# p8x-memory-card.net
KiCad netlist of a schematic drawn in EAGLE
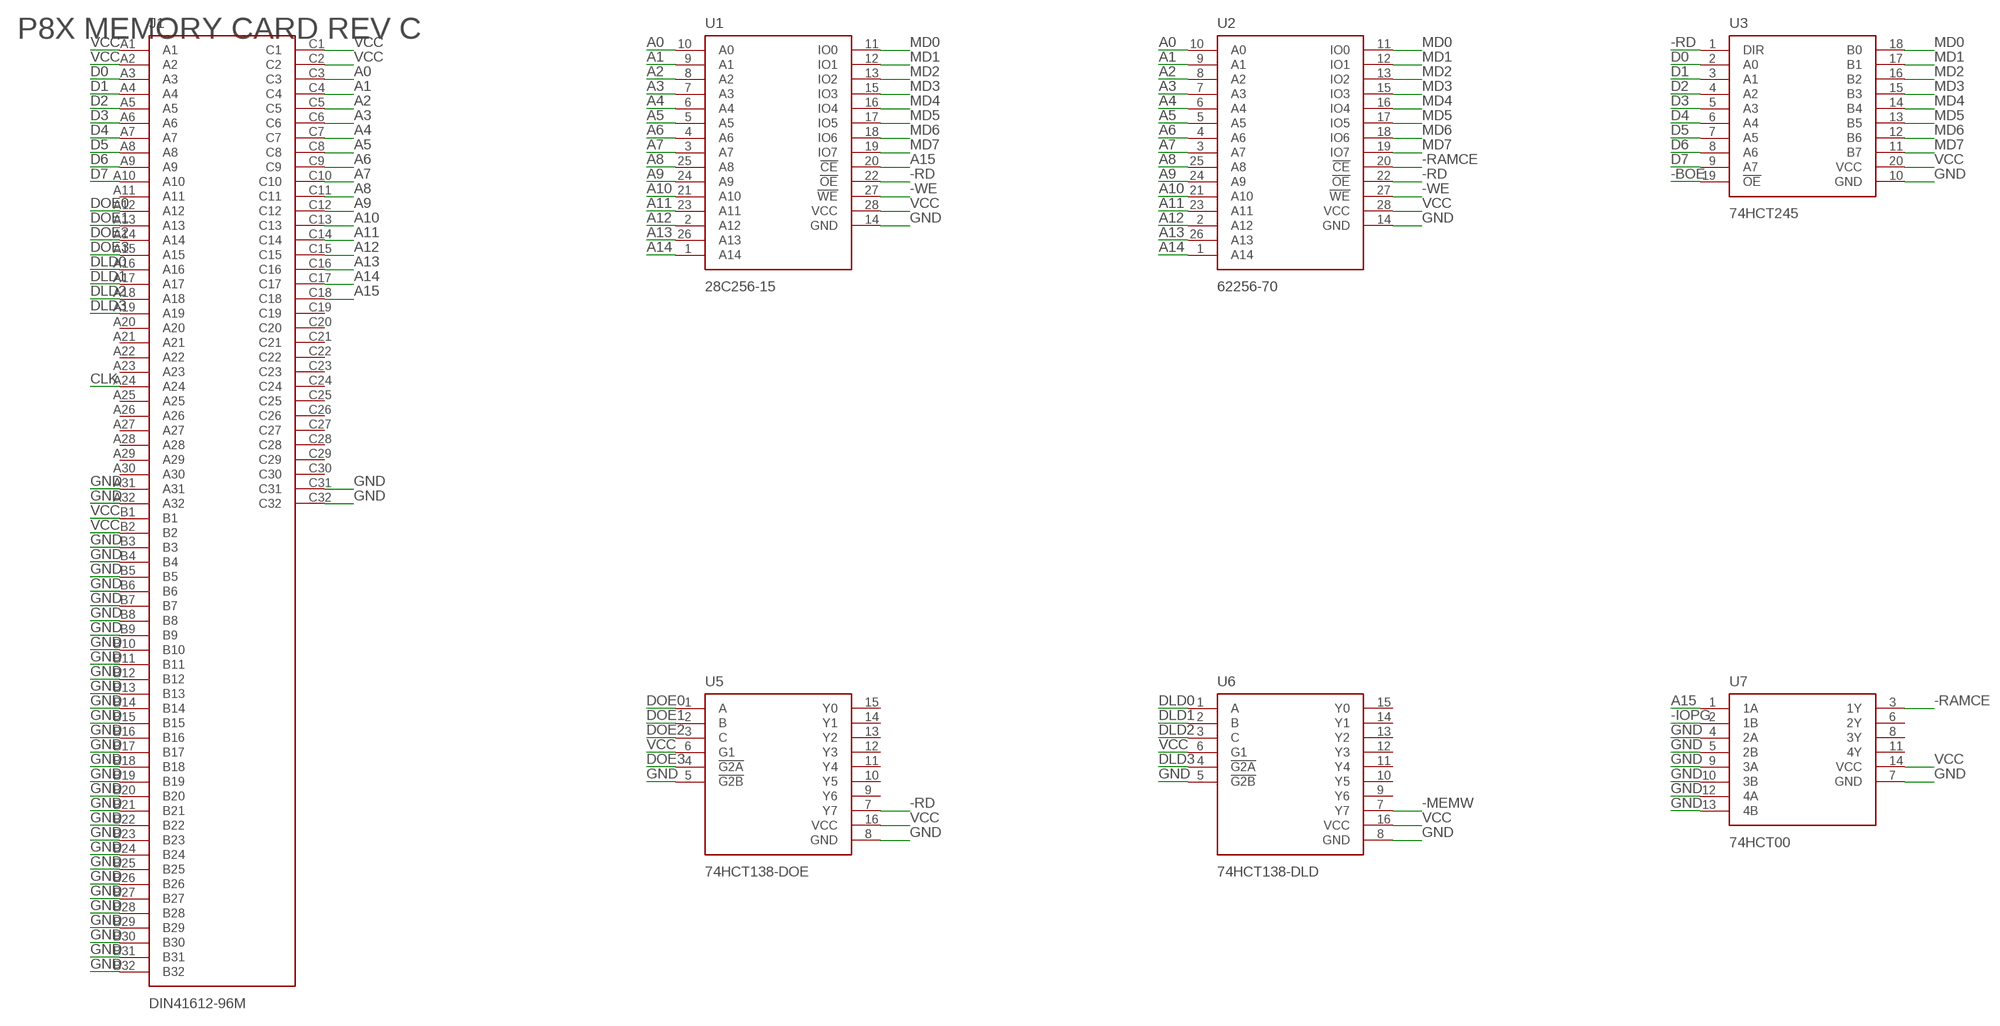
[diagram p0: schematic, sheet 1, part 1 of 2]
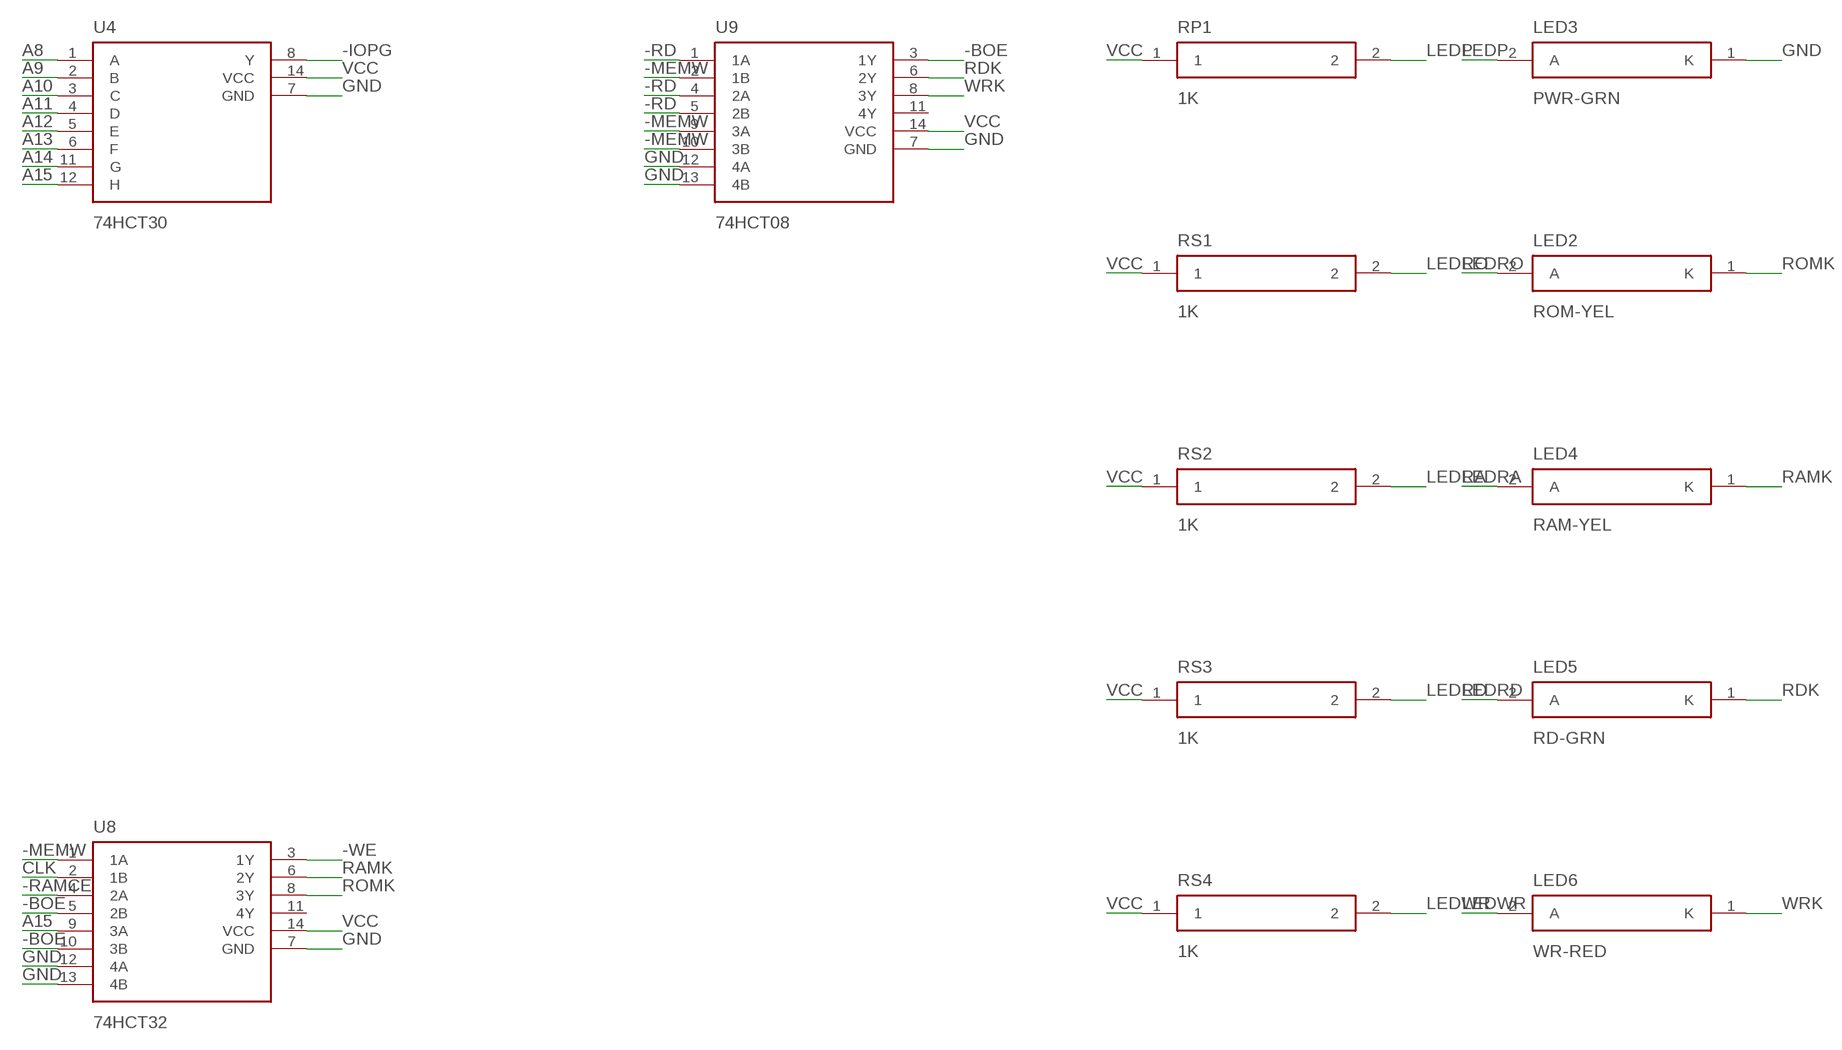
[diagram p1: schematic, sheet 1, part 2 of 2]

(export (version "E")
  (design (tool "Eeschema 10.0.6"))
  (components
    (comp (ref "J1")
      (value "DIN41612-96M")
      (footprint "eagle-import:DIN96")
      (libsource (lib "eagle-import") (part "DIN96"))
    )
    (comp (ref "LED2")
      (value "ROM-YEL")
      (footprint "eagle-import:LED5")
      (libsource (lib "eagle-import") (part "LED"))
    )
    (comp (ref "LED3")
      (value "PWR-GRN")
      (footprint "eagle-import:LED5")
      (libsource (lib "eagle-import") (part "LED"))
    )
    (comp (ref "LED4")
      (value "RAM-YEL")
      (footprint "eagle-import:LED5")
      (libsource (lib "eagle-import") (part "LED"))
    )
    (comp (ref "LED5")
      (value "RD-GRN")
      (footprint "eagle-import:LED5")
      (libsource (lib "eagle-import") (part "LED"))
    )
    (comp (ref "LED6")
      (value "WR-RED")
      (footprint "eagle-import:LED5")
      (libsource (lib "eagle-import") (part "LED"))
    )
    (comp (ref "RP1")
      (value "1K")
      (footprint "eagle-import:R_AXIAL")
      (libsource (lib "eagle-import") (part "RES"))
    )
    (comp (ref "RS1")
      (value "1K")
      (footprint "eagle-import:R_AXIAL")
      (libsource (lib "eagle-import") (part "RES"))
    )
    (comp (ref "RS2")
      (value "1K")
      (footprint "eagle-import:R_AXIAL")
      (libsource (lib "eagle-import") (part "RES"))
    )
    (comp (ref "RS3")
      (value "1K")
      (footprint "eagle-import:R_AXIAL")
      (libsource (lib "eagle-import") (part "RES"))
    )
    (comp (ref "RS4")
      (value "1K")
      (footprint "eagle-import:R_AXIAL")
      (libsource (lib "eagle-import") (part "RES"))
    )
    (comp (ref "U1")
      (value "28C256-15")
      (footprint "eagle-import:DIP28W")
      (libsource (lib "eagle-import") (part "MEM28K8"))
    )
    (comp (ref "U2")
      (value "62256-70")
      (footprint "eagle-import:DIP28W")
      (libsource (lib "eagle-import") (part "MEM28K8"))
    )
    (comp (ref "U3")
      (value "74HCT245")
      (footprint "eagle-import:DIP20")
      (libsource (lib "eagle-import") (part "74245"))
    )
    (comp (ref "U4")
      (value "74HCT30")
      (footprint "eagle-import:DIP14")
      (libsource (lib "eagle-import") (part "7430"))
    )
    (comp (ref "U5")
      (value "74HCT138-DOE")
      (footprint "eagle-import:DIP16")
      (libsource (lib "eagle-import") (part "74138"))
    )
    (comp (ref "U6")
      (value "74HCT138-DLD")
      (footprint "eagle-import:DIP16")
      (libsource (lib "eagle-import") (part "74138"))
    )
    (comp (ref "U7")
      (value "74HCT00")
      (footprint "eagle-import:DIP14")
      (libsource (lib "eagle-import") (part "GATES14"))
    )
    (comp (ref "U8")
      (value "74HCT32")
      (footprint "eagle-import:DIP14")
      (libsource (lib "eagle-import") (part "GATES14"))
    )
    (comp (ref "U9")
      (value "74HCT08")
      (footprint "eagle-import:DIP14")
      (libsource (lib "eagle-import") (part "GATES14"))
    )
  )
  (nets
    (net (code "1") (name "/-BOE") (class "Default")
      (node (ref "U3") (pin "19") (pinfunction "~{OE}_19") (pintype "bidirectional"))
      (node (ref "U8") (pin "10") (pinfunction "3B_10") (pintype "bidirectional"))
      (node (ref "U8") (pin "5") (pinfunction "2B_5") (pintype "bidirectional"))
      (node (ref "U9") (pin "3") (pinfunction "1Y_3") (pintype "bidirectional"))
    )
    (net (code "2") (name "/-IOPG") (class "Default")
      (node (ref "U4") (pin "8") (pinfunction "Y_8") (pintype "bidirectional"))
      (node (ref "U7") (pin "2") (pinfunction "1B_2") (pintype "bidirectional"))
    )
    (net (code "3") (name "/-MEMW") (class "Default")
      (node (ref "U6") (pin "7") (pinfunction "Y7_7") (pintype "bidirectional"))
      (node (ref "U8") (pin "1") (pinfunction "1A_1") (pintype "bidirectional"))
      (node (ref "U9") (pin "10") (pinfunction "3B_10") (pintype "bidirectional"))
      (node (ref "U9") (pin "2") (pinfunction "1B_2") (pintype "bidirectional"))
      (node (ref "U9") (pin "9") (pinfunction "3A_9") (pintype "bidirectional"))
    )
    (net (code "4") (name "/-RAMCE") (class "Default")
      (node (ref "U2") (pin "20") (pinfunction "~{CE}_20") (pintype "bidirectional"))
      (node (ref "U7") (pin "3") (pinfunction "1Y_3") (pintype "bidirectional"))
      (node (ref "U8") (pin "4") (pinfunction "2A_4") (pintype "bidirectional"))
    )
    (net (code "5") (name "/-RD") (class "Default")
      (node (ref "U1") (pin "22") (pinfunction "~{OE}_22") (pintype "bidirectional"))
      (node (ref "U2") (pin "22") (pinfunction "~{OE}_22") (pintype "bidirectional"))
      (node (ref "U3") (pin "1") (pinfunction "DIR_1") (pintype "bidirectional"))
      (node (ref "U5") (pin "7") (pinfunction "Y7_7") (pintype "bidirectional"))
      (node (ref "U9") (pin "1") (pinfunction "1A_1") (pintype "bidirectional"))
      (node (ref "U9") (pin "4") (pinfunction "2A_4") (pintype "bidirectional"))
      (node (ref "U9") (pin "5") (pinfunction "2B_5") (pintype "bidirectional"))
    )
    (net (code "6") (name "/-WE") (class "Default")
      (node (ref "U1") (pin "27") (pinfunction "~{WE}_27") (pintype "bidirectional"))
      (node (ref "U2") (pin "27") (pinfunction "~{WE}_27") (pintype "bidirectional"))
      (node (ref "U8") (pin "3") (pinfunction "1Y_3") (pintype "bidirectional"))
    )
    (net (code "7") (name "/A0") (class "Default")
      (node (ref "J1") (pin "C3") (pinfunction "C3_C3") (pintype "bidirectional"))
      (node (ref "U1") (pin "10") (pinfunction "A0_10") (pintype "bidirectional"))
      (node (ref "U2") (pin "10") (pinfunction "A0_10") (pintype "bidirectional"))
    )
    (net (code "8") (name "/A1") (class "Default")
      (node (ref "J1") (pin "C4") (pinfunction "C4_C4") (pintype "bidirectional"))
      (node (ref "U1") (pin "9") (pinfunction "A1_9") (pintype "bidirectional"))
      (node (ref "U2") (pin "9") (pinfunction "A1_9") (pintype "bidirectional"))
    )
    (net (code "9") (name "/A2") (class "Default")
      (node (ref "J1") (pin "C5") (pinfunction "C5_C5") (pintype "bidirectional"))
      (node (ref "U1") (pin "8") (pinfunction "A2_8") (pintype "bidirectional"))
      (node (ref "U2") (pin "8") (pinfunction "A2_8") (pintype "bidirectional"))
    )
    (net (code "10") (name "/A3") (class "Default")
      (node (ref "J1") (pin "C6") (pinfunction "C6_C6") (pintype "bidirectional"))
      (node (ref "U1") (pin "7") (pinfunction "A3_7") (pintype "bidirectional"))
      (node (ref "U2") (pin "7") (pinfunction "A3_7") (pintype "bidirectional"))
    )
    (net (code "11") (name "/A4") (class "Default")
      (node (ref "J1") (pin "C7") (pinfunction "C7_C7") (pintype "bidirectional"))
      (node (ref "U1") (pin "6") (pinfunction "A4_6") (pintype "bidirectional"))
      (node (ref "U2") (pin "6") (pinfunction "A4_6") (pintype "bidirectional"))
    )
    (net (code "12") (name "/A5") (class "Default")
      (node (ref "J1") (pin "C8") (pinfunction "C8_C8") (pintype "bidirectional"))
      (node (ref "U1") (pin "5") (pinfunction "A5_5") (pintype "bidirectional"))
      (node (ref "U2") (pin "5") (pinfunction "A5_5") (pintype "bidirectional"))
    )
    (net (code "13") (name "/A6") (class "Default")
      (node (ref "J1") (pin "C9") (pinfunction "C9_C9") (pintype "bidirectional"))
      (node (ref "U1") (pin "4") (pinfunction "A6_4") (pintype "bidirectional"))
      (node (ref "U2") (pin "4") (pinfunction "A6_4") (pintype "bidirectional"))
    )
    (net (code "14") (name "/A7") (class "Default")
      (node (ref "J1") (pin "C10") (pinfunction "C10_C10") (pintype "bidirectional"))
      (node (ref "U1") (pin "3") (pinfunction "A7_3") (pintype "bidirectional"))
      (node (ref "U2") (pin "3") (pinfunction "A7_3") (pintype "bidirectional"))
    )
    (net (code "15") (name "/A8") (class "Default")
      (node (ref "J1") (pin "C11") (pinfunction "C11_C11") (pintype "bidirectional"))
      (node (ref "U1") (pin "25") (pinfunction "A8_25") (pintype "bidirectional"))
      (node (ref "U2") (pin "25") (pinfunction "A8_25") (pintype "bidirectional"))
      (node (ref "U4") (pin "1") (pinfunction "A_1") (pintype "bidirectional"))
    )
    (net (code "16") (name "/A9") (class "Default")
      (node (ref "J1") (pin "C12") (pinfunction "C12_C12") (pintype "bidirectional"))
      (node (ref "U1") (pin "24") (pinfunction "A9_24") (pintype "bidirectional"))
      (node (ref "U2") (pin "24") (pinfunction "A9_24") (pintype "bidirectional"))
      (node (ref "U4") (pin "2") (pinfunction "B_2") (pintype "bidirectional"))
    )
    (net (code "17") (name "/A10") (class "Default")
      (node (ref "J1") (pin "C13") (pinfunction "C13_C13") (pintype "bidirectional"))
      (node (ref "U1") (pin "21") (pinfunction "A10_21") (pintype "bidirectional"))
      (node (ref "U2") (pin "21") (pinfunction "A10_21") (pintype "bidirectional"))
      (node (ref "U4") (pin "3") (pinfunction "C_3") (pintype "bidirectional"))
    )
    (net (code "18") (name "/A11") (class "Default")
      (node (ref "J1") (pin "C14") (pinfunction "C14_C14") (pintype "bidirectional"))
      (node (ref "U1") (pin "23") (pinfunction "A11_23") (pintype "bidirectional"))
      (node (ref "U2") (pin "23") (pinfunction "A11_23") (pintype "bidirectional"))
      (node (ref "U4") (pin "4") (pinfunction "D_4") (pintype "bidirectional"))
    )
    (net (code "19") (name "/A12") (class "Default")
      (node (ref "J1") (pin "C15") (pinfunction "C15_C15") (pintype "bidirectional"))
      (node (ref "U1") (pin "2") (pinfunction "A12_2") (pintype "bidirectional"))
      (node (ref "U2") (pin "2") (pinfunction "A12_2") (pintype "bidirectional"))
      (node (ref "U4") (pin "5") (pinfunction "E_5") (pintype "bidirectional"))
    )
    (net (code "20") (name "/A13") (class "Default")
      (node (ref "J1") (pin "C16") (pinfunction "C16_C16") (pintype "bidirectional"))
      (node (ref "U1") (pin "26") (pinfunction "A13_26") (pintype "bidirectional"))
      (node (ref "U2") (pin "26") (pinfunction "A13_26") (pintype "bidirectional"))
      (node (ref "U4") (pin "6") (pinfunction "F_6") (pintype "bidirectional"))
    )
    (net (code "21") (name "/A14") (class "Default")
      (node (ref "J1") (pin "C17") (pinfunction "C17_C17") (pintype "bidirectional"))
      (node (ref "U1") (pin "1") (pinfunction "A14_1") (pintype "bidirectional"))
      (node (ref "U2") (pin "1") (pinfunction "A14_1") (pintype "bidirectional"))
      (node (ref "U4") (pin "11") (pinfunction "G_11") (pintype "bidirectional"))
    )
    (net (code "22") (name "/A15") (class "Default")
      (node (ref "J1") (pin "C18") (pinfunction "C18_C18") (pintype "bidirectional"))
      (node (ref "U1") (pin "20") (pinfunction "~{CE}_20") (pintype "bidirectional"))
      (node (ref "U4") (pin "12") (pinfunction "H_12") (pintype "bidirectional"))
      (node (ref "U7") (pin "1") (pinfunction "1A_1") (pintype "bidirectional"))
      (node (ref "U8") (pin "9") (pinfunction "3A_9") (pintype "bidirectional"))
    )
    (net (code "23") (name "/CLK") (class "Default")
      (node (ref "J1") (pin "A24") (pinfunction "A24_A24") (pintype "bidirectional"))
      (node (ref "U8") (pin "2") (pinfunction "1B_2") (pintype "bidirectional"))
    )
    (net (code "24") (name "/D0") (class "Default")
      (node (ref "J1") (pin "A3") (pinfunction "A3_A3") (pintype "bidirectional"))
      (node (ref "U3") (pin "2") (pinfunction "A0_2") (pintype "bidirectional"))
    )
    (net (code "25") (name "/D1") (class "Default")
      (node (ref "J1") (pin "A4") (pinfunction "A4_A4") (pintype "bidirectional"))
      (node (ref "U3") (pin "3") (pinfunction "A1_3") (pintype "bidirectional"))
    )
    (net (code "26") (name "/D2") (class "Default")
      (node (ref "J1") (pin "A5") (pinfunction "A5_A5") (pintype "bidirectional"))
      (node (ref "U3") (pin "4") (pinfunction "A2_4") (pintype "bidirectional"))
    )
    (net (code "27") (name "/D3") (class "Default")
      (node (ref "J1") (pin "A6") (pinfunction "A6_A6") (pintype "bidirectional"))
      (node (ref "U3") (pin "5") (pinfunction "A3_5") (pintype "bidirectional"))
    )
    (net (code "28") (name "/D4") (class "Default")
      (node (ref "J1") (pin "A7") (pinfunction "A7_A7") (pintype "bidirectional"))
      (node (ref "U3") (pin "6") (pinfunction "A4_6") (pintype "bidirectional"))
    )
    (net (code "29") (name "/D5") (class "Default")
      (node (ref "J1") (pin "A8") (pinfunction "A8_A8") (pintype "bidirectional"))
      (node (ref "U3") (pin "7") (pinfunction "A5_7") (pintype "bidirectional"))
    )
    (net (code "30") (name "/D6") (class "Default")
      (node (ref "J1") (pin "A9") (pinfunction "A9_A9") (pintype "bidirectional"))
      (node (ref "U3") (pin "8") (pinfunction "A6_8") (pintype "bidirectional"))
    )
    (net (code "31") (name "/D7") (class "Default")
      (node (ref "J1") (pin "A10") (pinfunction "A10_A10") (pintype "bidirectional"))
      (node (ref "U3") (pin "9") (pinfunction "A7_9") (pintype "bidirectional"))
    )
    (net (code "32") (name "/DLD0") (class "Default")
      (node (ref "J1") (pin "A16") (pinfunction "A16_A16") (pintype "bidirectional"))
      (node (ref "U6") (pin "1") (pinfunction "A_1") (pintype "bidirectional"))
    )
    (net (code "33") (name "/DLD1") (class "Default")
      (node (ref "J1") (pin "A17") (pinfunction "A17_A17") (pintype "bidirectional"))
      (node (ref "U6") (pin "2") (pinfunction "B_2") (pintype "bidirectional"))
    )
    (net (code "34") (name "/DLD2") (class "Default")
      (node (ref "J1") (pin "A18") (pinfunction "A18_A18") (pintype "bidirectional"))
      (node (ref "U6") (pin "3") (pinfunction "C_3") (pintype "bidirectional"))
    )
    (net (code "35") (name "/DLD3") (class "Default")
      (node (ref "J1") (pin "A19") (pinfunction "A19_A19") (pintype "bidirectional"))
      (node (ref "U6") (pin "4") (pinfunction "~{G2A}_4") (pintype "bidirectional"))
    )
    (net (code "36") (name "/DOE0") (class "Default")
      (node (ref "J1") (pin "A12") (pinfunction "A12_A12") (pintype "bidirectional"))
      (node (ref "U5") (pin "1") (pinfunction "A_1") (pintype "bidirectional"))
    )
    (net (code "37") (name "/DOE1") (class "Default")
      (node (ref "J1") (pin "A13") (pinfunction "A13_A13") (pintype "bidirectional"))
      (node (ref "U5") (pin "2") (pinfunction "B_2") (pintype "bidirectional"))
    )
    (net (code "38") (name "/DOE2") (class "Default")
      (node (ref "J1") (pin "A14") (pinfunction "A14_A14") (pintype "bidirectional"))
      (node (ref "U5") (pin "3") (pinfunction "C_3") (pintype "bidirectional"))
    )
    (net (code "39") (name "/DOE3") (class "Default")
      (node (ref "J1") (pin "A15") (pinfunction "A15_A15") (pintype "bidirectional"))
      (node (ref "U5") (pin "4") (pinfunction "~{G2A}_4") (pintype "bidirectional"))
    )
    (net (code "40") (name "/GND") (class "Default")
      (node (ref "J1") (pin "A31") (pinfunction "A31_A31") (pintype "bidirectional"))
      (node (ref "J1") (pin "A32") (pinfunction "A32_A32") (pintype "bidirectional"))
      (node (ref "J1") (pin "B10") (pinfunction "B10_B10") (pintype "bidirectional"))
      (node (ref "J1") (pin "B11") (pinfunction "B11_B11") (pintype "bidirectional"))
      (node (ref "J1") (pin "B12") (pinfunction "B12_B12") (pintype "bidirectional"))
      (node (ref "J1") (pin "B13") (pinfunction "B13_B13") (pintype "bidirectional"))
      (node (ref "J1") (pin "B14") (pinfunction "B14_B14") (pintype "bidirectional"))
      (node (ref "J1") (pin "B15") (pinfunction "B15_B15") (pintype "bidirectional"))
      (node (ref "J1") (pin "B16") (pinfunction "B16_B16") (pintype "bidirectional"))
      (node (ref "J1") (pin "B17") (pinfunction "B17_B17") (pintype "bidirectional"))
      (node (ref "J1") (pin "B18") (pinfunction "B18_B18") (pintype "bidirectional"))
      (node (ref "J1") (pin "B19") (pinfunction "B19_B19") (pintype "bidirectional"))
      (node (ref "J1") (pin "B20") (pinfunction "B20_B20") (pintype "bidirectional"))
      (node (ref "J1") (pin "B21") (pinfunction "B21_B21") (pintype "bidirectional"))
      (node (ref "J1") (pin "B22") (pinfunction "B22_B22") (pintype "bidirectional"))
      (node (ref "J1") (pin "B23") (pinfunction "B23_B23") (pintype "bidirectional"))
      (node (ref "J1") (pin "B24") (pinfunction "B24_B24") (pintype "bidirectional"))
      (node (ref "J1") (pin "B25") (pinfunction "B25_B25") (pintype "bidirectional"))
      (node (ref "J1") (pin "B26") (pinfunction "B26_B26") (pintype "bidirectional"))
      (node (ref "J1") (pin "B27") (pinfunction "B27_B27") (pintype "bidirectional"))
      (node (ref "J1") (pin "B28") (pinfunction "B28_B28") (pintype "bidirectional"))
      (node (ref "J1") (pin "B29") (pinfunction "B29_B29") (pintype "bidirectional"))
      (node (ref "J1") (pin "B3") (pinfunction "B3_B3") (pintype "bidirectional"))
      (node (ref "J1") (pin "B30") (pinfunction "B30_B30") (pintype "bidirectional"))
      (node (ref "J1") (pin "B31") (pinfunction "B31_B31") (pintype "bidirectional"))
      (node (ref "J1") (pin "B32") (pinfunction "B32_B32") (pintype "bidirectional"))
      (node (ref "J1") (pin "B4") (pinfunction "B4_B4") (pintype "bidirectional"))
      (node (ref "J1") (pin "B5") (pinfunction "B5_B5") (pintype "bidirectional"))
      (node (ref "J1") (pin "B6") (pinfunction "B6_B6") (pintype "bidirectional"))
      (node (ref "J1") (pin "B7") (pinfunction "B7_B7") (pintype "bidirectional"))
      (node (ref "J1") (pin "B8") (pinfunction "B8_B8") (pintype "bidirectional"))
      (node (ref "J1") (pin "B9") (pinfunction "B9_B9") (pintype "bidirectional"))
      (node (ref "J1") (pin "C31") (pinfunction "C31_C31") (pintype "bidirectional"))
      (node (ref "J1") (pin "C32") (pinfunction "C32_C32") (pintype "bidirectional"))
      (node (ref "LED3") (pin "1") (pinfunction "K_1") (pintype "bidirectional"))
      (node (ref "U1") (pin "14") (pinfunction "GND_14") (pintype "bidirectional"))
      (node (ref "U2") (pin "14") (pinfunction "GND_14") (pintype "bidirectional"))
      (node (ref "U3") (pin "10") (pinfunction "GND_10") (pintype "bidirectional"))
      (node (ref "U4") (pin "7") (pinfunction "GND_7") (pintype "bidirectional"))
      (node (ref "U5") (pin "5") (pinfunction "~{G2B}_5") (pintype "bidirectional"))
      (node (ref "U5") (pin "8") (pinfunction "GND_8") (pintype "bidirectional"))
      (node (ref "U6") (pin "5") (pinfunction "~{G2B}_5") (pintype "bidirectional"))
      (node (ref "U6") (pin "8") (pinfunction "GND_8") (pintype "bidirectional"))
      (node (ref "U7") (pin "10") (pinfunction "3B_10") (pintype "bidirectional"))
      (node (ref "U7") (pin "12") (pinfunction "4A_12") (pintype "bidirectional"))
      (node (ref "U7") (pin "13") (pinfunction "4B_13") (pintype "bidirectional"))
      (node (ref "U7") (pin "4") (pinfunction "2A_4") (pintype "bidirectional"))
      (node (ref "U7") (pin "5") (pinfunction "2B_5") (pintype "bidirectional"))
      (node (ref "U7") (pin "7") (pinfunction "GND_7") (pintype "bidirectional"))
      (node (ref "U7") (pin "9") (pinfunction "3A_9") (pintype "bidirectional"))
      (node (ref "U8") (pin "12") (pinfunction "4A_12") (pintype "bidirectional"))
      (node (ref "U8") (pin "13") (pinfunction "4B_13") (pintype "bidirectional"))
      (node (ref "U8") (pin "7") (pinfunction "GND_7") (pintype "bidirectional"))
      (node (ref "U9") (pin "12") (pinfunction "4A_12") (pintype "bidirectional"))
      (node (ref "U9") (pin "13") (pinfunction "4B_13") (pintype "bidirectional"))
      (node (ref "U9") (pin "7") (pinfunction "GND_7") (pintype "bidirectional"))
    )
    (net (code "41") (name "/LEDP") (class "Default")
      (node (ref "LED3") (pin "2") (pinfunction "A_2") (pintype "bidirectional"))
      (node (ref "RP1") (pin "2") (pinfunction "2_2") (pintype "bidirectional"))
    )
    (net (code "42") (name "/LEDRA") (class "Default")
      (node (ref "LED4") (pin "2") (pinfunction "A_2") (pintype "bidirectional"))
      (node (ref "RS2") (pin "2") (pinfunction "2_2") (pintype "bidirectional"))
    )
    (net (code "43") (name "/LEDRD") (class "Default")
      (node (ref "LED5") (pin "2") (pinfunction "A_2") (pintype "bidirectional"))
      (node (ref "RS3") (pin "2") (pinfunction "2_2") (pintype "bidirectional"))
    )
    (net (code "44") (name "/LEDRO") (class "Default")
      (node (ref "LED2") (pin "2") (pinfunction "A_2") (pintype "bidirectional"))
      (node (ref "RS1") (pin "2") (pinfunction "2_2") (pintype "bidirectional"))
    )
    (net (code "45") (name "/LEDWR") (class "Default")
      (node (ref "LED6") (pin "2") (pinfunction "A_2") (pintype "bidirectional"))
      (node (ref "RS4") (pin "2") (pinfunction "2_2") (pintype "bidirectional"))
    )
    (net (code "46") (name "/MD0") (class "Default")
      (node (ref "U1") (pin "11") (pinfunction "IO0_11") (pintype "bidirectional"))
      (node (ref "U2") (pin "11") (pinfunction "IO0_11") (pintype "bidirectional"))
      (node (ref "U3") (pin "18") (pinfunction "B0_18") (pintype "bidirectional"))
    )
    (net (code "47") (name "/MD1") (class "Default")
      (node (ref "U1") (pin "12") (pinfunction "IO1_12") (pintype "bidirectional"))
      (node (ref "U2") (pin "12") (pinfunction "IO1_12") (pintype "bidirectional"))
      (node (ref "U3") (pin "17") (pinfunction "B1_17") (pintype "bidirectional"))
    )
    (net (code "48") (name "/MD2") (class "Default")
      (node (ref "U1") (pin "13") (pinfunction "IO2_13") (pintype "bidirectional"))
      (node (ref "U2") (pin "13") (pinfunction "IO2_13") (pintype "bidirectional"))
      (node (ref "U3") (pin "16") (pinfunction "B2_16") (pintype "bidirectional"))
    )
    (net (code "49") (name "/MD3") (class "Default")
      (node (ref "U1") (pin "15") (pinfunction "IO3_15") (pintype "bidirectional"))
      (node (ref "U2") (pin "15") (pinfunction "IO3_15") (pintype "bidirectional"))
      (node (ref "U3") (pin "15") (pinfunction "B3_15") (pintype "bidirectional"))
    )
    (net (code "50") (name "/MD4") (class "Default")
      (node (ref "U1") (pin "16") (pinfunction "IO4_16") (pintype "bidirectional"))
      (node (ref "U2") (pin "16") (pinfunction "IO4_16") (pintype "bidirectional"))
      (node (ref "U3") (pin "14") (pinfunction "B4_14") (pintype "bidirectional"))
    )
    (net (code "51") (name "/MD5") (class "Default")
      (node (ref "U1") (pin "17") (pinfunction "IO5_17") (pintype "bidirectional"))
      (node (ref "U2") (pin "17") (pinfunction "IO5_17") (pintype "bidirectional"))
      (node (ref "U3") (pin "13") (pinfunction "B5_13") (pintype "bidirectional"))
    )
    (net (code "52") (name "/MD6") (class "Default")
      (node (ref "U1") (pin "18") (pinfunction "IO6_18") (pintype "bidirectional"))
      (node (ref "U2") (pin "18") (pinfunction "IO6_18") (pintype "bidirectional"))
      (node (ref "U3") (pin "12") (pinfunction "B6_12") (pintype "bidirectional"))
    )
    (net (code "53") (name "/MD7") (class "Default")
      (node (ref "U1") (pin "19") (pinfunction "IO7_19") (pintype "bidirectional"))
      (node (ref "U2") (pin "19") (pinfunction "IO7_19") (pintype "bidirectional"))
      (node (ref "U3") (pin "11") (pinfunction "B7_11") (pintype "bidirectional"))
    )
    (net (code "54") (name "/RAMK") (class "Default")
      (node (ref "LED4") (pin "1") (pinfunction "K_1") (pintype "bidirectional"))
      (node (ref "U8") (pin "6") (pinfunction "2Y_6") (pintype "bidirectional"))
    )
    (net (code "55") (name "/RDK") (class "Default")
      (node (ref "LED5") (pin "1") (pinfunction "K_1") (pintype "bidirectional"))
      (node (ref "U9") (pin "6") (pinfunction "2Y_6") (pintype "bidirectional"))
    )
    (net (code "56") (name "/ROMK") (class "Default")
      (node (ref "LED2") (pin "1") (pinfunction "K_1") (pintype "bidirectional"))
      (node (ref "U8") (pin "8") (pinfunction "3Y_8") (pintype "bidirectional"))
    )
    (net (code "57") (name "/VCC") (class "Default")
      (node (ref "J1") (pin "A1") (pinfunction "A1_A1") (pintype "bidirectional"))
      (node (ref "J1") (pin "A2") (pinfunction "A2_A2") (pintype "bidirectional"))
      (node (ref "J1") (pin "B1") (pinfunction "B1_B1") (pintype "bidirectional"))
      (node (ref "J1") (pin "B2") (pinfunction "B2_B2") (pintype "bidirectional"))
      (node (ref "J1") (pin "C1") (pinfunction "C1_C1") (pintype "bidirectional"))
      (node (ref "J1") (pin "C2") (pinfunction "C2_C2") (pintype "bidirectional"))
      (node (ref "RP1") (pin "1") (pinfunction "1_1") (pintype "bidirectional"))
      (node (ref "RS1") (pin "1") (pinfunction "1_1") (pintype "bidirectional"))
      (node (ref "RS2") (pin "1") (pinfunction "1_1") (pintype "bidirectional"))
      (node (ref "RS3") (pin "1") (pinfunction "1_1") (pintype "bidirectional"))
      (node (ref "RS4") (pin "1") (pinfunction "1_1") (pintype "bidirectional"))
      (node (ref "U1") (pin "28") (pinfunction "VCC_28") (pintype "bidirectional"))
      (node (ref "U2") (pin "28") (pinfunction "VCC_28") (pintype "bidirectional"))
      (node (ref "U3") (pin "20") (pinfunction "VCC_20") (pintype "bidirectional"))
      (node (ref "U4") (pin "14") (pinfunction "VCC_14") (pintype "bidirectional"))
      (node (ref "U5") (pin "16") (pinfunction "VCC_16") (pintype "bidirectional"))
      (node (ref "U5") (pin "6") (pinfunction "G1_6") (pintype "bidirectional"))
      (node (ref "U6") (pin "16") (pinfunction "VCC_16") (pintype "bidirectional"))
      (node (ref "U6") (pin "6") (pinfunction "G1_6") (pintype "bidirectional"))
      (node (ref "U7") (pin "14") (pinfunction "VCC_14") (pintype "bidirectional"))
      (node (ref "U8") (pin "14") (pinfunction "VCC_14") (pintype "bidirectional"))
      (node (ref "U9") (pin "14") (pinfunction "VCC_14") (pintype "bidirectional"))
    )
    (net (code "58") (name "/WRK") (class "Default")
      (node (ref "LED6") (pin "1") (pinfunction "K_1") (pintype "bidirectional"))
      (node (ref "U9") (pin "8") (pinfunction "3Y_8") (pintype "bidirectional"))
    )
    (net (code "59") (name "unconnected-(J1-PadA11)") (class "Default")
      (node (ref "J1") (pin "A11") (pinfunction "A11_A11") (pintype "bidirectional"))
    )
    (net (code "60") (name "unconnected-(J1-PadA20)") (class "Default")
      (node (ref "J1") (pin "A20") (pinfunction "A20_A20") (pintype "bidirectional"))
    )
    (net (code "61") (name "unconnected-(J1-PadA21)") (class "Default")
      (node (ref "J1") (pin "A21") (pinfunction "A21_A21") (pintype "bidirectional"))
    )
    (net (code "62") (name "unconnected-(J1-PadA22)") (class "Default")
      (node (ref "J1") (pin "A22") (pinfunction "A22_A22") (pintype "bidirectional"))
    )
    (net (code "63") (name "unconnected-(J1-PadA23)") (class "Default")
      (node (ref "J1") (pin "A23") (pinfunction "A23_A23") (pintype "bidirectional"))
    )
    (net (code "64") (name "unconnected-(J1-PadA25)") (class "Default")
      (node (ref "J1") (pin "A25") (pinfunction "A25_A25") (pintype "bidirectional"))
    )
    (net (code "65") (name "unconnected-(J1-PadA26)") (class "Default")
      (node (ref "J1") (pin "A26") (pinfunction "A26_A26") (pintype "bidirectional"))
    )
    (net (code "66") (name "unconnected-(J1-PadA27)") (class "Default")
      (node (ref "J1") (pin "A27") (pinfunction "A27_A27") (pintype "bidirectional"))
    )
    (net (code "67") (name "unconnected-(J1-PadA28)") (class "Default")
      (node (ref "J1") (pin "A28") (pinfunction "A28_A28") (pintype "bidirectional"))
    )
    (net (code "68") (name "unconnected-(J1-PadA29)") (class "Default")
      (node (ref "J1") (pin "A29") (pinfunction "A29_A29") (pintype "bidirectional"))
    )
    (net (code "69") (name "unconnected-(J1-PadA30)") (class "Default")
      (node (ref "J1") (pin "A30") (pinfunction "A30_A30") (pintype "bidirectional"))
    )
    (net (code "70") (name "unconnected-(J1-PadC19)") (class "Default")
      (node (ref "J1") (pin "C19") (pinfunction "C19_C19") (pintype "bidirectional"))
    )
    (net (code "71") (name "unconnected-(J1-PadC20)") (class "Default")
      (node (ref "J1") (pin "C20") (pinfunction "C20_C20") (pintype "bidirectional"))
    )
    (net (code "72") (name "unconnected-(J1-PadC21)") (class "Default")
      (node (ref "J1") (pin "C21") (pinfunction "C21_C21") (pintype "bidirectional"))
    )
    (net (code "73") (name "unconnected-(J1-PadC22)") (class "Default")
      (node (ref "J1") (pin "C22") (pinfunction "C22_C22") (pintype "bidirectional"))
    )
    (net (code "74") (name "unconnected-(J1-PadC23)") (class "Default")
      (node (ref "J1") (pin "C23") (pinfunction "C23_C23") (pintype "bidirectional"))
    )
    (net (code "75") (name "unconnected-(J1-PadC24)") (class "Default")
      (node (ref "J1") (pin "C24") (pinfunction "C24_C24") (pintype "bidirectional"))
    )
    (net (code "76") (name "unconnected-(J1-PadC25)") (class "Default")
      (node (ref "J1") (pin "C25") (pinfunction "C25_C25") (pintype "bidirectional"))
    )
    (net (code "77") (name "unconnected-(J1-PadC26)") (class "Default")
      (node (ref "J1") (pin "C26") (pinfunction "C26_C26") (pintype "bidirectional"))
    )
    (net (code "78") (name "unconnected-(J1-PadC27)") (class "Default")
      (node (ref "J1") (pin "C27") (pinfunction "C27_C27") (pintype "bidirectional"))
    )
    (net (code "79") (name "unconnected-(J1-PadC28)") (class "Default")
      (node (ref "J1") (pin "C28") (pinfunction "C28_C28") (pintype "bidirectional"))
    )
    (net (code "80") (name "unconnected-(J1-PadC29)") (class "Default")
      (node (ref "J1") (pin "C29") (pinfunction "C29_C29") (pintype "bidirectional"))
    )
    (net (code "81") (name "unconnected-(J1-PadC30)") (class "Default")
      (node (ref "J1") (pin "C30") (pinfunction "C30_C30") (pintype "bidirectional"))
    )
    (net (code "82") (name "unconnected-(U5-Y0-Pad15)") (class "Default")
      (node (ref "U5") (pin "15") (pinfunction "Y0_15") (pintype "bidirectional"))
    )
    (net (code "83") (name "unconnected-(U5-Y1-Pad14)") (class "Default")
      (node (ref "U5") (pin "14") (pinfunction "Y1_14") (pintype "bidirectional"))
    )
    (net (code "84") (name "unconnected-(U5-Y2-Pad13)") (class "Default")
      (node (ref "U5") (pin "13") (pinfunction "Y2_13") (pintype "bidirectional"))
    )
    (net (code "85") (name "unconnected-(U5-Y3-Pad12)") (class "Default")
      (node (ref "U5") (pin "12") (pinfunction "Y3_12") (pintype "bidirectional"))
    )
    (net (code "86") (name "unconnected-(U5-Y4-Pad11)") (class "Default")
      (node (ref "U5") (pin "11") (pinfunction "Y4_11") (pintype "bidirectional"))
    )
    (net (code "87") (name "unconnected-(U5-Y5-Pad10)") (class "Default")
      (node (ref "U5") (pin "10") (pinfunction "Y5_10") (pintype "bidirectional"))
    )
    (net (code "88") (name "unconnected-(U5-Y6-Pad9)") (class "Default")
      (node (ref "U5") (pin "9") (pinfunction "Y6_9") (pintype "bidirectional"))
    )
    (net (code "89") (name "unconnected-(U6-Y0-Pad15)") (class "Default")
      (node (ref "U6") (pin "15") (pinfunction "Y0_15") (pintype "bidirectional"))
    )
    (net (code "90") (name "unconnected-(U6-Y1-Pad14)") (class "Default")
      (node (ref "U6") (pin "14") (pinfunction "Y1_14") (pintype "bidirectional"))
    )
    (net (code "91") (name "unconnected-(U6-Y2-Pad13)") (class "Default")
      (node (ref "U6") (pin "13") (pinfunction "Y2_13") (pintype "bidirectional"))
    )
    (net (code "92") (name "unconnected-(U6-Y3-Pad12)") (class "Default")
      (node (ref "U6") (pin "12") (pinfunction "Y3_12") (pintype "bidirectional"))
    )
    (net (code "93") (name "unconnected-(U6-Y4-Pad11)") (class "Default")
      (node (ref "U6") (pin "11") (pinfunction "Y4_11") (pintype "bidirectional"))
    )
    (net (code "94") (name "unconnected-(U6-Y5-Pad10)") (class "Default")
      (node (ref "U6") (pin "10") (pinfunction "Y5_10") (pintype "bidirectional"))
    )
    (net (code "95") (name "unconnected-(U6-Y6-Pad9)") (class "Default")
      (node (ref "U6") (pin "9") (pinfunction "Y6_9") (pintype "bidirectional"))
    )
    (net (code "96") (name "unconnected-(U7-2Y-Pad6)") (class "Default")
      (node (ref "U7") (pin "6") (pinfunction "2Y_6") (pintype "bidirectional"))
    )
    (net (code "97") (name "unconnected-(U7-3Y-Pad8)") (class "Default")
      (node (ref "U7") (pin "8") (pinfunction "3Y_8") (pintype "bidirectional"))
    )
    (net (code "98") (name "unconnected-(U7-4Y-Pad11)") (class "Default")
      (node (ref "U7") (pin "11") (pinfunction "4Y_11") (pintype "bidirectional"))
    )
    (net (code "99") (name "unconnected-(U8-4Y-Pad11)") (class "Default")
      (node (ref "U8") (pin "11") (pinfunction "4Y_11") (pintype "bidirectional"))
    )
    (net (code "100") (name "unconnected-(U9-4Y-Pad11)") (class "Default")
      (node (ref "U9") (pin "11") (pinfunction "4Y_11") (pintype "bidirectional"))
    )
  )
)
